# Single_Pulse_Gen.net
KiCad netlist of a schematic drawn in Altium Designer
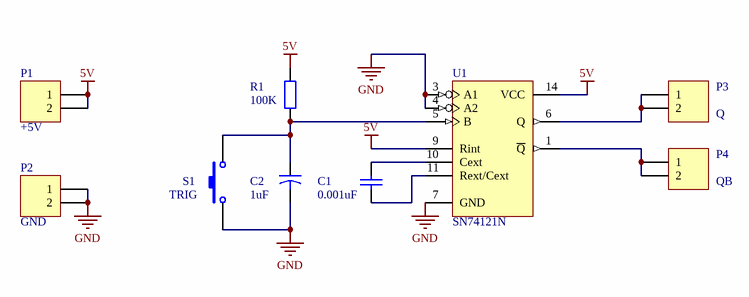
[diagram p0: Single Pulse Gen.SchDoc]

(export (version "E")
  (design (tool "Eeschema 10.0.6"))
  (components
    (comp (ref "C1")
      (value "0.001uF")
      (footprint "RAD-0.1")
      (description "Capacitor")
      (fields (field (name "PUBLISHER") "Altium Limited"))
      (libsource (lib "Miscellaneous Devices") (part "Cap"))
    )
    (comp (ref "C2")
      (value "1uF")
      (footprint "CAPPR2-5X11")
      (description "Capacitor")
      (fields (field (name "PUBLISHER") "Altium Limited"))
      (libsource (lib "Miscellaneous Devices") (part "Cap2"))
    )
    (comp (ref "P1")
      (value "+5V")
      (footprint "HDR1X2")
      (description "Header, 2-Pin")
      (fields (field (name "PUBLISHER") "Altium Limited"))
      (libsource (lib "Miscellaneous Connectors") (part "Header 2"))
    )
    (comp (ref "P2")
      (value "GND")
      (footprint "HDR1X2")
      (description "Header, 2-Pin")
      (fields (field (name "PUBLISHER") "Altium Limited"))
      (libsource (lib "Miscellaneous Connectors") (part "Header 2"))
    )
    (comp (ref "P3")
      (value "Q")
      (footprint "HDR1X2")
      (description "Header, 2-Pin")
      (fields (field (name "PUBLISHER") "Altium Limited"))
      (libsource (lib "") (part "Header 2_1"))
    )
    (comp (ref "P4")
      (value "QB")
      (footprint "HDR1X2")
      (description "Header, 2-Pin")
      (fields (field (name "PUBLISHER") "Altium Limited"))
      (libsource (lib "") (part "Header 2_1"))
    )
    (comp (ref "R1")
      (value "100K")
      (footprint "AXIAL-0.4")
      (description "Resistor")
      (fields (field (name "PUBLISHER") "Altium Limited"))
      (libsource (lib "Miscellaneous Devices") (part "Res2"))
    )
    (comp (ref "S1")
      (value "TRIG")
      (footprint "RESET SW")
      (description "Switch")
      (fields (field (name "PUBLISHER") "Altium Limited"))
      (libsource (lib "Miscellaneous Devices") (part "SW-PB"))
    )
    (comp (ref "U1")
      (value "SN74121N")
      (footprint "N014")
      (description "Monostable Multivibrator with Schmitt-Trigger Inputs")
      (fields (field (name "PUBLISHER") "Altium Limited"))
      (libsource (lib "TI Logic Multivibrator") (part "SN74121N"))
    )
  )
  (nets
    (net (code "1") (name "5V") (class "Default")
      (node (ref "P1") (pin "1") (pinfunction "1_1") (pintype "passive"))
      (node (ref "P1") (pin "2") (pinfunction "2_2") (pintype "passive"))
      (node (ref "R1") (pin "2") (pinfunction "2_2") (pintype "passive"))
      (node (ref "U1") (pin "14") (pinfunction "VCC_14") (pintype "power_in"))
      (node (ref "U1") (pin "9") (pinfunction "Rint_9") (pintype "passive"))
    )
    (net (code "2") (name "GND") (class "Default")
      (node (ref "C2") (pin "2") (pinfunction "2_2") (pintype "passive"))
      (node (ref "P2") (pin "1") (pinfunction "1_1") (pintype "passive"))
      (node (ref "P2") (pin "2") (pinfunction "2_2") (pintype "passive"))
      (node (ref "S1") (pin "1") (pinfunction "1_1") (pintype "passive"))
      (node (ref "U1") (pin "3") (pinfunction "A1_3") (pintype "input"))
      (node (ref "U1") (pin "4") (pinfunction "A2_4") (pintype "input"))
      (node (ref "U1") (pin "7") (pinfunction "GND_7") (pintype "power_in"))
    )
    (net (code "3") (name "Net-(U1-B)") (class "Default")
      (node (ref "C2") (pin "1") (pinfunction "1_1") (pintype "passive"))
      (node (ref "R1") (pin "1") (pinfunction "1_1") (pintype "passive"))
      (node (ref "S1") (pin "2") (pinfunction "2_2") (pintype "passive"))
      (node (ref "U1") (pin "5") (pinfunction "B_5") (pintype "input"))
    )
    (net (code "4") (name "Net-(U1-Cext)") (class "Default")
      (node (ref "C1") (pin "2") (pinfunction "2_2") (pintype "passive"))
      (node (ref "U1") (pin "10") (pinfunction "Cext_10") (pintype "passive"))
    )
    (net (code "5") (name "Net-(U1-Q)") (class "Default")
      (node (ref "P3") (pin "1") (pinfunction "1_1") (pintype "passive"))
      (node (ref "P3") (pin "2") (pinfunction "2_2") (pintype "passive"))
      (node (ref "U1") (pin "6") (pinfunction "Q_6") (pintype "output"))
    )
    (net (code "6") (name "Net-(U1-Rext{slash}Cext)") (class "Default")
      (node (ref "C1") (pin "1") (pinfunction "1_1") (pintype "passive"))
      (node (ref "U1") (pin "11") (pinfunction "Rext/Cext_11") (pintype "passive"))
    )
    (net (code "7") (name "Net-(U1-~{Q})") (class "Default")
      (node (ref "P4") (pin "1") (pinfunction "1_1") (pintype "passive"))
      (node (ref "P4") (pin "2") (pinfunction "2_2") (pintype "passive"))
      (node (ref "U1") (pin "1") (pinfunction "~{Q}_1") (pintype "output"))
    )
  )
)
